# LEDs.net
KiCad netlist of a schematic drawn in EAGLE
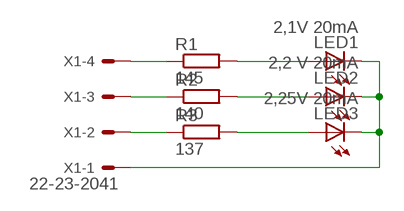
[diagram p0: schematic, sheet 1]

(export (version "E")
  (design (tool "Eeschema 10.0.6"))
  (components
    (comp (ref "LED1")
      (value "2,1V 20mA")
      (footprint "eagle-import:LED5MM")
      (libsource (lib "eagle-import") (part "LED5MM"))
    )
    (comp (ref "LED2")
      (value "2,2 V 20mA")
      (footprint "eagle-import:LED5MM")
      (libsource (lib "eagle-import") (part "LED5MM"))
    )
    (comp (ref "LED3")
      (value "2,25V 20mA")
      (footprint "eagle-import:LED5MM")
      (libsource (lib "eagle-import") (part "LED5MM"))
    )
    (comp (ref "R1")
      (value "145")
      (footprint "eagle-import:0207_10")
      (libsource (lib "eagle-import") (part "R-EU_0207/10"))
    )
    (comp (ref "R2")
      (value "140")
      (footprint "eagle-import:0207_10")
      (libsource (lib "eagle-import") (part "R-EU_0207/10"))
    )
    (comp (ref "R3")
      (value "137")
      (footprint "eagle-import:0207_10")
      (libsource (lib "eagle-import") (part "R-EU_0207/10"))
    )
    (comp (ref "X1")
      (value "22-23-2041")
      (footprint "eagle-import:22-23-2041")
      (fields (field (name "MF") "MOLEX"))
      (libsource (lib "eagle-import") (part "22-23-2041"))
    )
  )
  (nets
    (net (code "1") (name "Net-(LED1-C)") (class "Default")
      (node (ref "LED1") (pin "K") (pinfunction "C_K") (pintype "passive"))
      (node (ref "LED2") (pin "K") (pinfunction "C_K") (pintype "passive"))
      (node (ref "LED3") (pin "K") (pinfunction "C_K") (pintype "passive"))
      (node (ref "X1") (pin "1") (pinfunction "S_1") (pintype "passive"))
    )
    (net (code "2") (name "Net-(LED1-PadA)") (class "Default")
      (node (ref "LED1") (pin "A") (pinfunction "A_A") (pintype "passive"))
      (node (ref "R1") (pin "2") (pinfunction "2_2") (pintype "passive"))
    )
    (net (code "3") (name "Net-(LED2-PadA)") (class "Default")
      (node (ref "LED2") (pin "A") (pinfunction "A_A") (pintype "passive"))
      (node (ref "R2") (pin "2") (pinfunction "2_2") (pintype "passive"))
    )
    (net (code "4") (name "Net-(LED3-PadA)") (class "Default")
      (node (ref "LED3") (pin "A") (pinfunction "A_A") (pintype "passive"))
      (node (ref "R3") (pin "2") (pinfunction "2_2") (pintype "passive"))
    )
    (net (code "5") (name "Net-(X1B-S)") (class "Default")
      (node (ref "R3") (pin "1") (pinfunction "1_1") (pintype "passive"))
      (node (ref "X1") (pin "2") (pinfunction "S_2") (pintype "passive"))
    )
    (net (code "6") (name "Net-(X1C-S)") (class "Default")
      (node (ref "R2") (pin "1") (pinfunction "1_1") (pintype "passive"))
      (node (ref "X1") (pin "3") (pinfunction "S_3") (pintype "passive"))
    )
    (net (code "7") (name "Net-(X1D-S)") (class "Default")
      (node (ref "R1") (pin "1") (pinfunction "1_1") (pintype "passive"))
      (node (ref "X1") (pin "4") (pinfunction "S_4") (pintype "passive"))
    )
  )
)
